# Pinduino-Nano-WPC-adaptor-panalized_AR.net
KiCad netlist of a schematic drawn in EAGLE
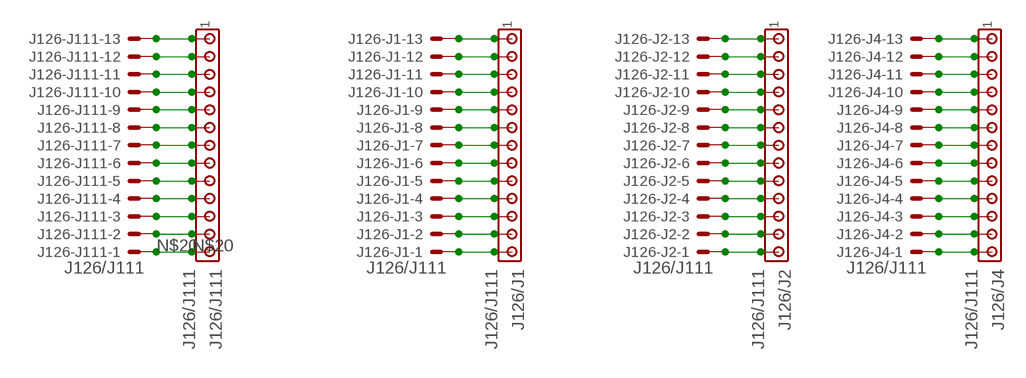
[diagram p0: schematic, sheet 1]

(export (version "E")
  (design (tool "Eeschema 10.0.6"))
  (components
    (comp (ref "J126-J1")
      (value "J126/J111")
      (footprint "eagle-import:KK-156-13")
      (libsource (lib "eagle-import") (part "KK-156-13"))
    )
    (comp (ref "J126-J2")
      (value "J126/J111")
      (footprint "eagle-import:KK-156-13")
      (libsource (lib "eagle-import") (part "KK-156-13"))
    )
    (comp (ref "J126-J4")
      (value "J126/J111")
      (footprint "eagle-import:KK-156-13")
      (libsource (lib "eagle-import") (part "KK-156-13"))
    )
    (comp (ref "J126-J111")
      (value "J126/J111")
      (footprint "eagle-import:KK-156-13")
      (libsource (lib "eagle-import") (part "KK-156-13"))
    )
    (comp (ref "J126/J1")
      (value "J126/J111")
      (footprint "eagle-import:1X13MTA")
      (libsource (lib "eagle-import") (part "MTA13-156"))
    )
    (comp (ref "J126/J2")
      (value "J126/J111")
      (footprint "eagle-import:1X13MTA")
      (libsource (lib "eagle-import") (part "MTA13-156"))
    )
    (comp (ref "J126/J4")
      (value "J126/J111")
      (footprint "eagle-import:1X13MTA")
      (libsource (lib "eagle-import") (part "MTA13-156"))
    )
    (comp (ref "J126/J111")
      (value "J126/J111")
      (footprint "eagle-import:1X13MTA")
      (libsource (lib "eagle-import") (part "MTA13-156"))
    )
  )
  (nets
    (net (code "1") (name "/N$20") (class "Default")
      (node (ref "J126-J111") (pin "2") (pinfunction "S_2") (pintype "passive"))
      (node (ref "J126/J111") (pin "12") (pinfunction "12_12") (pintype "passive"))
    )
    (net (code "2") (name "Net-(J126-J1A-S)") (class "Default")
      (node (ref "J126-J1") (pin "1") (pinfunction "S_1") (pintype "passive"))
      (node (ref "J126/J1") (pin "13") (pinfunction "13_13") (pintype "passive"))
    )
    (net (code "3") (name "Net-(J126-J1B-S)") (class "Default")
      (node (ref "J126-J1") (pin "10") (pinfunction "S_10") (pintype "passive"))
      (node (ref "J126/J1") (pin "4") (pinfunction "4_4") (pintype "passive"))
    )
    (net (code "4") (name "Net-(J126-J1C-S)") (class "Default")
      (node (ref "J126-J1") (pin "11") (pinfunction "S_11") (pintype "passive"))
      (node (ref "J126/J1") (pin "3") (pinfunction "3_3") (pintype "passive"))
    )
    (net (code "5") (name "Net-(J126-J1D-S)") (class "Default")
      (node (ref "J126-J1") (pin "12") (pinfunction "S_12") (pintype "passive"))
      (node (ref "J126/J1") (pin "2") (pinfunction "2_2") (pintype "passive"))
    )
    (net (code "6") (name "Net-(J126-J1E-S)") (class "Default")
      (node (ref "J126-J1") (pin "13") (pinfunction "S_13") (pintype "passive"))
      (node (ref "J126/J1") (pin "1") (pinfunction "1_1") (pintype "passive"))
    )
    (net (code "7") (name "Net-(J126-J1F-S)") (class "Default")
      (node (ref "J126-J1") (pin "2") (pinfunction "S_2") (pintype "passive"))
      (node (ref "J126/J1") (pin "12") (pinfunction "12_12") (pintype "passive"))
    )
    (net (code "8") (name "Net-(J126-J1G-S)") (class "Default")
      (node (ref "J126-J1") (pin "3") (pinfunction "S_3") (pintype "passive"))
      (node (ref "J126/J1") (pin "11") (pinfunction "11_11") (pintype "passive"))
    )
    (net (code "9") (name "Net-(J126-J1H-S)") (class "Default")
      (node (ref "J126-J1") (pin "4") (pinfunction "S_4") (pintype "passive"))
      (node (ref "J126/J1") (pin "10") (pinfunction "10_10") (pintype "passive"))
    )
    (net (code "10") (name "Net-(J126-J1I-S)") (class "Default")
      (node (ref "J126-J1") (pin "5") (pinfunction "S_5") (pintype "passive"))
      (node (ref "J126/J1") (pin "9") (pinfunction "9_9") (pintype "passive"))
    )
    (net (code "11") (name "Net-(J126-J1J-S)") (class "Default")
      (node (ref "J126-J1") (pin "6") (pinfunction "S_6") (pintype "passive"))
      (node (ref "J126/J1") (pin "8") (pinfunction "8_8") (pintype "passive"))
    )
    (net (code "12") (name "Net-(J126-J1K-S)") (class "Default")
      (node (ref "J126-J1") (pin "7") (pinfunction "S_7") (pintype "passive"))
      (node (ref "J126/J1") (pin "7") (pinfunction "7_7") (pintype "passive"))
    )
    (net (code "13") (name "Net-(J126-J1L-S)") (class "Default")
      (node (ref "J126-J1") (pin "8") (pinfunction "S_8") (pintype "passive"))
      (node (ref "J126/J1") (pin "6") (pinfunction "6_6") (pintype "passive"))
    )
    (net (code "14") (name "Net-(J126-J1M-S)") (class "Default")
      (node (ref "J126-J1") (pin "9") (pinfunction "S_9") (pintype "passive"))
      (node (ref "J126/J1") (pin "5") (pinfunction "5_5") (pintype "passive"))
    )
    (net (code "15") (name "Net-(J126-J2A-S)") (class "Default")
      (node (ref "J126-J2") (pin "1") (pinfunction "S_1") (pintype "passive"))
      (node (ref "J126/J2") (pin "13") (pinfunction "13_13") (pintype "passive"))
    )
    (net (code "16") (name "Net-(J126-J2B-S)") (class "Default")
      (node (ref "J126-J2") (pin "10") (pinfunction "S_10") (pintype "passive"))
      (node (ref "J126/J2") (pin "4") (pinfunction "4_4") (pintype "passive"))
    )
    (net (code "17") (name "Net-(J126-J2C-S)") (class "Default")
      (node (ref "J126-J2") (pin "11") (pinfunction "S_11") (pintype "passive"))
      (node (ref "J126/J2") (pin "3") (pinfunction "3_3") (pintype "passive"))
    )
    (net (code "18") (name "Net-(J126-J2D-S)") (class "Default")
      (node (ref "J126-J2") (pin "12") (pinfunction "S_12") (pintype "passive"))
      (node (ref "J126/J2") (pin "2") (pinfunction "2_2") (pintype "passive"))
    )
    (net (code "19") (name "Net-(J126-J2E-S)") (class "Default")
      (node (ref "J126-J2") (pin "13") (pinfunction "S_13") (pintype "passive"))
      (node (ref "J126/J2") (pin "1") (pinfunction "1_1") (pintype "passive"))
    )
    (net (code "20") (name "Net-(J126-J2F-S)") (class "Default")
      (node (ref "J126-J2") (pin "2") (pinfunction "S_2") (pintype "passive"))
      (node (ref "J126/J2") (pin "12") (pinfunction "12_12") (pintype "passive"))
    )
    (net (code "21") (name "Net-(J126-J2G-S)") (class "Default")
      (node (ref "J126-J2") (pin "3") (pinfunction "S_3") (pintype "passive"))
      (node (ref "J126/J2") (pin "11") (pinfunction "11_11") (pintype "passive"))
    )
    (net (code "22") (name "Net-(J126-J2H-S)") (class "Default")
      (node (ref "J126-J2") (pin "4") (pinfunction "S_4") (pintype "passive"))
      (node (ref "J126/J2") (pin "10") (pinfunction "10_10") (pintype "passive"))
    )
    (net (code "23") (name "Net-(J126-J2I-S)") (class "Default")
      (node (ref "J126-J2") (pin "5") (pinfunction "S_5") (pintype "passive"))
      (node (ref "J126/J2") (pin "9") (pinfunction "9_9") (pintype "passive"))
    )
    (net (code "24") (name "Net-(J126-J2J-S)") (class "Default")
      (node (ref "J126-J2") (pin "6") (pinfunction "S_6") (pintype "passive"))
      (node (ref "J126/J2") (pin "8") (pinfunction "8_8") (pintype "passive"))
    )
    (net (code "25") (name "Net-(J126-J2K-S)") (class "Default")
      (node (ref "J126-J2") (pin "7") (pinfunction "S_7") (pintype "passive"))
      (node (ref "J126/J2") (pin "7") (pinfunction "7_7") (pintype "passive"))
    )
    (net (code "26") (name "Net-(J126-J2L-S)") (class "Default")
      (node (ref "J126-J2") (pin "8") (pinfunction "S_8") (pintype "passive"))
      (node (ref "J126/J2") (pin "6") (pinfunction "6_6") (pintype "passive"))
    )
    (net (code "27") (name "Net-(J126-J2M-S)") (class "Default")
      (node (ref "J126-J2") (pin "9") (pinfunction "S_9") (pintype "passive"))
      (node (ref "J126/J2") (pin "5") (pinfunction "5_5") (pintype "passive"))
    )
    (net (code "28") (name "Net-(J126-J4A-S)") (class "Default")
      (node (ref "J126-J4") (pin "1") (pinfunction "S_1") (pintype "passive"))
      (node (ref "J126/J4") (pin "13") (pinfunction "13_13") (pintype "passive"))
    )
    (net (code "29") (name "Net-(J126-J4B-S)") (class "Default")
      (node (ref "J126-J4") (pin "10") (pinfunction "S_10") (pintype "passive"))
      (node (ref "J126/J4") (pin "4") (pinfunction "4_4") (pintype "passive"))
    )
    (net (code "30") (name "Net-(J126-J4C-S)") (class "Default")
      (node (ref "J126-J4") (pin "11") (pinfunction "S_11") (pintype "passive"))
      (node (ref "J126/J4") (pin "3") (pinfunction "3_3") (pintype "passive"))
    )
    (net (code "31") (name "Net-(J126-J4D-S)") (class "Default")
      (node (ref "J126-J4") (pin "12") (pinfunction "S_12") (pintype "passive"))
      (node (ref "J126/J4") (pin "2") (pinfunction "2_2") (pintype "passive"))
    )
    (net (code "32") (name "Net-(J126-J4E-S)") (class "Default")
      (node (ref "J126-J4") (pin "13") (pinfunction "S_13") (pintype "passive"))
      (node (ref "J126/J4") (pin "1") (pinfunction "1_1") (pintype "passive"))
    )
    (net (code "33") (name "Net-(J126-J4F-S)") (class "Default")
      (node (ref "J126-J4") (pin "2") (pinfunction "S_2") (pintype "passive"))
      (node (ref "J126/J4") (pin "12") (pinfunction "12_12") (pintype "passive"))
    )
    (net (code "34") (name "Net-(J126-J4G-S)") (class "Default")
      (node (ref "J126-J4") (pin "3") (pinfunction "S_3") (pintype "passive"))
      (node (ref "J126/J4") (pin "11") (pinfunction "11_11") (pintype "passive"))
    )
    (net (code "35") (name "Net-(J126-J4H-S)") (class "Default")
      (node (ref "J126-J4") (pin "4") (pinfunction "S_4") (pintype "passive"))
      (node (ref "J126/J4") (pin "10") (pinfunction "10_10") (pintype "passive"))
    )
    (net (code "36") (name "Net-(J126-J4I-S)") (class "Default")
      (node (ref "J126-J4") (pin "5") (pinfunction "S_5") (pintype "passive"))
      (node (ref "J126/J4") (pin "9") (pinfunction "9_9") (pintype "passive"))
    )
    (net (code "37") (name "Net-(J126-J4J-S)") (class "Default")
      (node (ref "J126-J4") (pin "6") (pinfunction "S_6") (pintype "passive"))
      (node (ref "J126/J4") (pin "8") (pinfunction "8_8") (pintype "passive"))
    )
    (net (code "38") (name "Net-(J126-J4K-S)") (class "Default")
      (node (ref "J126-J4") (pin "7") (pinfunction "S_7") (pintype "passive"))
      (node (ref "J126/J4") (pin "7") (pinfunction "7_7") (pintype "passive"))
    )
    (net (code "39") (name "Net-(J126-J4L-S)") (class "Default")
      (node (ref "J126-J4") (pin "8") (pinfunction "S_8") (pintype "passive"))
      (node (ref "J126/J4") (pin "6") (pinfunction "6_6") (pintype "passive"))
    )
    (net (code "40") (name "Net-(J126-J4M-S)") (class "Default")
      (node (ref "J126-J4") (pin "9") (pinfunction "S_9") (pintype "passive"))
      (node (ref "J126/J4") (pin "5") (pinfunction "5_5") (pintype "passive"))
    )
    (net (code "41") (name "Net-(J126-J111A-S)") (class "Default")
      (node (ref "J126-J111") (pin "1") (pinfunction "S_1") (pintype "passive"))
      (node (ref "J126/J111") (pin "13") (pinfunction "13_13") (pintype "passive"))
    )
    (net (code "42") (name "Net-(J126-J111B-S)") (class "Default")
      (node (ref "J126-J111") (pin "10") (pinfunction "S_10") (pintype "passive"))
      (node (ref "J126/J111") (pin "4") (pinfunction "4_4") (pintype "passive"))
    )
    (net (code "43") (name "Net-(J126-J111C-S)") (class "Default")
      (node (ref "J126-J111") (pin "11") (pinfunction "S_11") (pintype "passive"))
      (node (ref "J126/J111") (pin "3") (pinfunction "3_3") (pintype "passive"))
    )
    (net (code "44") (name "Net-(J126-J111D-S)") (class "Default")
      (node (ref "J126-J111") (pin "12") (pinfunction "S_12") (pintype "passive"))
      (node (ref "J126/J111") (pin "2") (pinfunction "2_2") (pintype "passive"))
    )
    (net (code "45") (name "Net-(J126-J111E-S)") (class "Default")
      (node (ref "J126-J111") (pin "13") (pinfunction "S_13") (pintype "passive"))
      (node (ref "J126/J111") (pin "1") (pinfunction "1_1") (pintype "passive"))
    )
    (net (code "46") (name "Net-(J126-J111G-S)") (class "Default")
      (node (ref "J126-J111") (pin "3") (pinfunction "S_3") (pintype "passive"))
      (node (ref "J126/J111") (pin "11") (pinfunction "11_11") (pintype "passive"))
    )
    (net (code "47") (name "Net-(J126-J111H-S)") (class "Default")
      (node (ref "J126-J111") (pin "4") (pinfunction "S_4") (pintype "passive"))
      (node (ref "J126/J111") (pin "10") (pinfunction "10_10") (pintype "passive"))
    )
    (net (code "48") (name "Net-(J126-J111I-S)") (class "Default")
      (node (ref "J126-J111") (pin "5") (pinfunction "S_5") (pintype "passive"))
      (node (ref "J126/J111") (pin "9") (pinfunction "9_9") (pintype "passive"))
    )
    (net (code "49") (name "Net-(J126-J111J-S)") (class "Default")
      (node (ref "J126-J111") (pin "6") (pinfunction "S_6") (pintype "passive"))
      (node (ref "J126/J111") (pin "8") (pinfunction "8_8") (pintype "passive"))
    )
    (net (code "50") (name "Net-(J126-J111K-S)") (class "Default")
      (node (ref "J126-J111") (pin "7") (pinfunction "S_7") (pintype "passive"))
      (node (ref "J126/J111") (pin "7") (pinfunction "7_7") (pintype "passive"))
    )
    (net (code "51") (name "Net-(J126-J111L-S)") (class "Default")
      (node (ref "J126-J111") (pin "8") (pinfunction "S_8") (pintype "passive"))
      (node (ref "J126/J111") (pin "6") (pinfunction "6_6") (pintype "passive"))
    )
    (net (code "52") (name "Net-(J126-J111M-S)") (class "Default")
      (node (ref "J126-J111") (pin "9") (pinfunction "S_9") (pintype "passive"))
      (node (ref "J126/J111") (pin "5") (pinfunction "5_5") (pintype "passive"))
    )
  )
)
